# Servo_buffer.net
KiCad netlist of a schematic drawn in Altium Designer
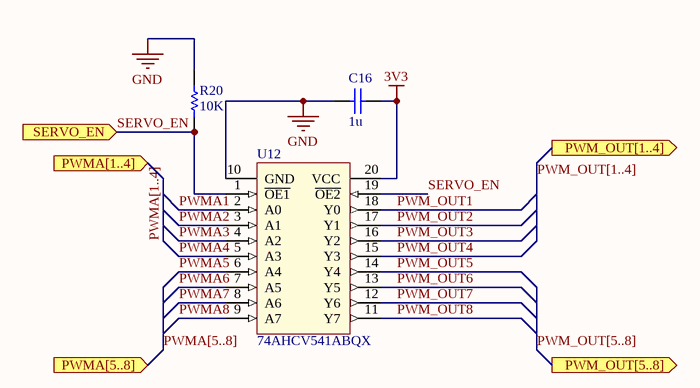
[diagram p0: Servo_buffer.SchDoc]

(export (version "E")
  (design (tool "Eeschema 10.0.6"))
  (components
    (comp (ref "C16")
      (value "1u")
      (footprint "CAPC1608X90N")
      (description "Capacitor")
      (fields (field (name "Comment") "Cap") (field (name "PUBLISHER") "Altium Limited"))
      (libsource (lib "IOBoard_Low") (part "Cap"))
    )
    (comp (ref "R20")
      (value "10K")
      (footprint "RESC1608X55N")
      (description "Resistor")
      (fields (field (name "Comment") "Res1") (field (name "PUBLISHER") "Altium Limited"))
      (libsource (lib "IOBoard_Low") (part "Res1"))
    )
    (comp (ref "U12")
      (value "74AHCV541ABQX")
      (footprint "TSSOP20_4.4mm")
      (description "Octal buffer/line driver; 3-state")
      (fields
        (field (name "SOURCE") "https://www.mouser.hk/ProductDetail/Nexperia/74AHCV244APWJ?qs=sGAEpiMZZMuiiWkaIwCK2bgmxBV%2FR64eEE4cbZSq%2Ff0=")
      )
      (libsource (lib "IOBoard_Low") (part "74AHCV541ABQX"))
    )
  )
  (nets
    (net (code "1") (name "/PWMA1") (class "Default")
      (node (ref "U12") (pin "2") (pinfunction "A0_2") (pintype "input"))
    )
    (net (code "2") (name "/PWMA2") (class "Default")
      (node (ref "U12") (pin "3") (pinfunction "A1_3") (pintype "input"))
    )
    (net (code "3") (name "/PWMA3") (class "Default")
      (node (ref "U12") (pin "4") (pinfunction "A2_4") (pintype "input"))
    )
    (net (code "4") (name "/PWMA4") (class "Default")
      (node (ref "U12") (pin "5") (pinfunction "A3_5") (pintype "input"))
    )
    (net (code "5") (name "/PWMA5") (class "Default")
      (node (ref "U12") (pin "6") (pinfunction "A4_6") (pintype "input"))
    )
    (net (code "6") (name "/PWMA6") (class "Default")
      (node (ref "U12") (pin "7") (pinfunction "A5_7") (pintype "input"))
    )
    (net (code "7") (name "/PWMA7") (class "Default")
      (node (ref "U12") (pin "8") (pinfunction "A6_8") (pintype "input"))
    )
    (net (code "8") (name "/PWMA8") (class "Default")
      (node (ref "U12") (pin "9") (pinfunction "A7_9") (pintype "input"))
    )
    (net (code "11") (name "/PWM_OUT1") (class "Default")
      (node (ref "U12") (pin "18") (pinfunction "Y0_18") (pintype "output"))
    )
    (net (code "12") (name "/PWM_OUT2") (class "Default")
      (node (ref "U12") (pin "17") (pinfunction "Y1_17") (pintype "output"))
    )
    (net (code "13") (name "/PWM_OUT3") (class "Default")
      (node (ref "U12") (pin "16") (pinfunction "Y2_16") (pintype "output"))
    )
    (net (code "14") (name "/PWM_OUT4") (class "Default")
      (node (ref "U12") (pin "15") (pinfunction "Y3_15") (pintype "output"))
    )
    (net (code "15") (name "/PWM_OUT5") (class "Default")
      (node (ref "U12") (pin "14") (pinfunction "Y4_14") (pintype "output"))
    )
    (net (code "16") (name "/PWM_OUT6") (class "Default")
      (node (ref "U12") (pin "13") (pinfunction "Y5_13") (pintype "output"))
    )
    (net (code "17") (name "/PWM_OUT7") (class "Default")
      (node (ref "U12") (pin "12") (pinfunction "Y6_12") (pintype "output"))
    )
    (net (code "18") (name "/PWM_OUT8") (class "Default")
      (node (ref "U12") (pin "11") (pinfunction "Y7_11") (pintype "output"))
    )
    (net (code "21") (name "/SERVO_EN") (class "Default")
      (node (ref "R20") (pin "1") (pinfunction "1_1") (pintype "passive"))
      (node (ref "U12") (pin "1") (pinfunction "~{OE1}_1") (pintype "input"))
      (node (ref "U12") (pin "19") (pinfunction "~{OE2}_19") (pintype "input"))
    )
    (net (code "22") (name "3V3") (class "Default")
      (node (ref "C16") (pin "2") (pinfunction "2_2") (pintype "passive"))
      (node (ref "U12") (pin "20") (pinfunction "VCC_20") (pintype "power_in"))
    )
    (net (code "23") (name "GND") (class "Default")
      (node (ref "C16") (pin "1") (pinfunction "1_1") (pintype "passive"))
      (node (ref "R20") (pin "2") (pinfunction "2_2") (pintype "passive"))
      (node (ref "U12") (pin "10") (pinfunction "GND_10") (pintype "power_in"))
    )
  )
)
